# Stazione_Meteo.net
KiCad netlist of a schematic drawn in EAGLE
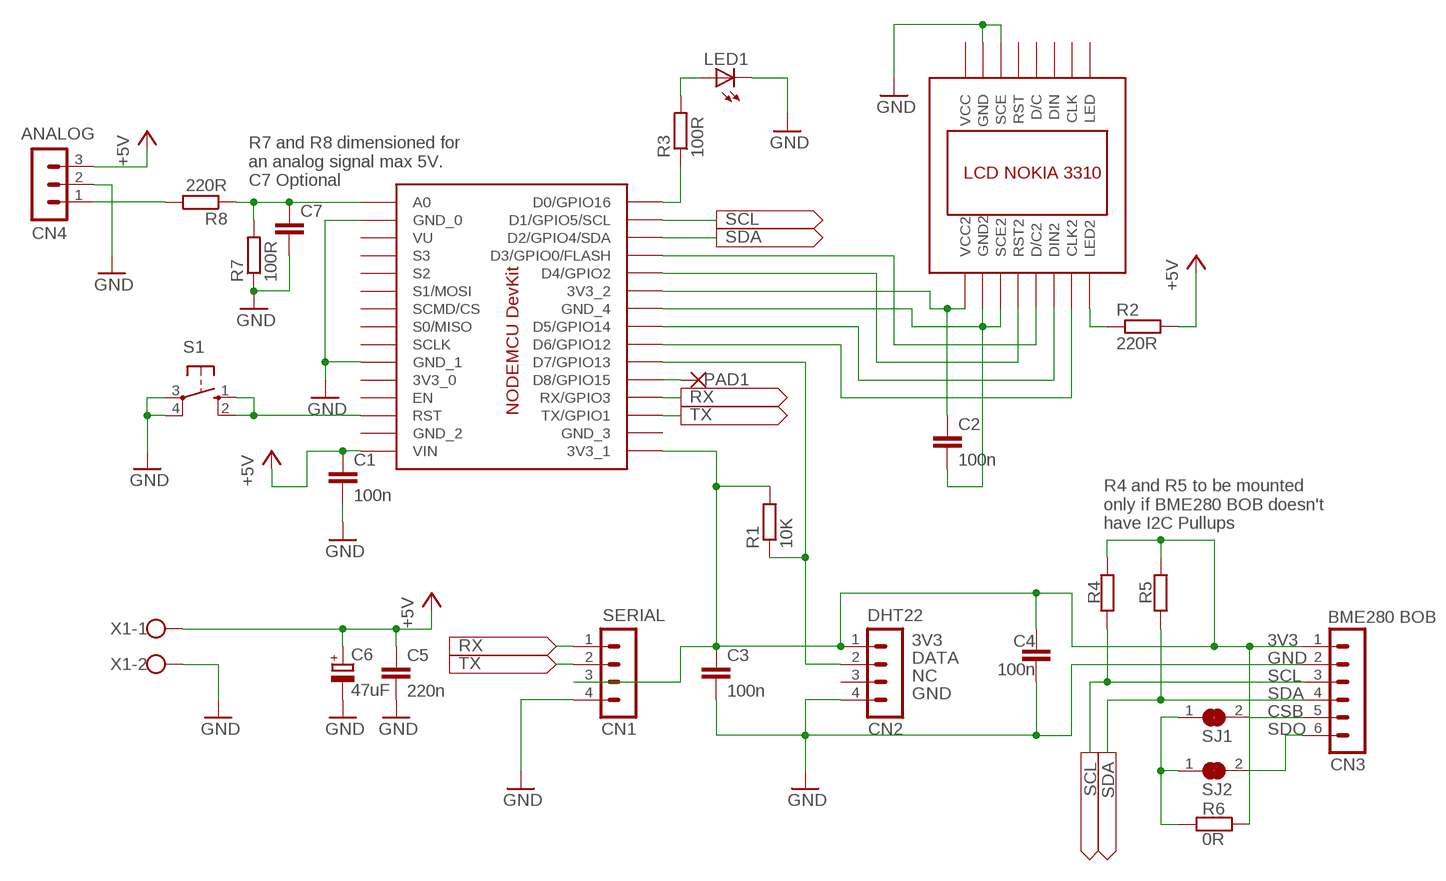
[diagram p0: schematic, sheet 1]

(export (version "E")
  (design (tool "Eeschema 10.0.6"))
  (components
    (comp (ref "C1")
      (value "100n")
      (footprint "eagle-import:C025-024X044")
      (libsource (lib "eagle-import") (part "C-EU025-024X044"))
    )
    (comp (ref "C2")
      (value "100n")
      (footprint "eagle-import:C025-024X044")
      (libsource (lib "eagle-import") (part "C-EU025-024X044"))
    )
    (comp (ref "C3")
      (value "100n")
      (footprint "eagle-import:C025-024X044")
      (libsource (lib "eagle-import") (part "C-EU025-024X044"))
    )
    (comp (ref "C4")
      (value "100n")
      (footprint "eagle-import:C025-024X044")
      (libsource (lib "eagle-import") (part "C-EU025-024X044"))
    )
    (comp (ref "C5")
      (value "220n")
      (footprint "eagle-import:C025-024X044")
      (libsource (lib "eagle-import") (part "C-EU025-024X044"))
    )
    (comp (ref "C6")
      (value "47uF")
      (footprint "eagle-import:E2,5-6E")
      (libsource (lib "eagle-import") (part "CPOL-EUE2,5-6E"))
    )
    (comp (ref "C7")
      (value "C-EU025-024X044")
      (footprint "eagle-import:C025-024X044")
      (libsource (lib "eagle-import") (part "C-EU025-024X044"))
    )
    (comp (ref "CN1")
      (value "MA04-1")
      (footprint "eagle-import:MA04-1")
      (libsource (lib "eagle-import") (part "MA04-1"))
    )
    (comp (ref "CN2")
      (value "MA04-1")
      (footprint "eagle-import:MA04-1")
      (libsource (lib "eagle-import") (part "MA04-1"))
    )
    (comp (ref "CN3")
      (value "MA06-1")
      (footprint "eagle-import:MA06-1")
      (libsource (lib "eagle-import") (part "MA06-1"))
    )
    (comp (ref "CN4")
      (value "MA03-1")
      (footprint "eagle-import:MA03-1")
      (libsource (lib "eagle-import") (part "MA03-1"))
    )
    (comp (ref "LED1")
      (value "LED5MM")
      (footprint "eagle-import:LED5MM")
      (libsource (lib "eagle-import") (part "LED5MM"))
    )
    (comp (ref "PAD1")
      (value "1,6/0,9")
      (footprint "eagle-import:1,6_0,9")
      (libsource (lib "eagle-import") (part "1,6/0,9"))
    )
    (comp (ref "R1")
      (value "10K")
      (footprint "eagle-import:0204_7")
      (libsource (lib "eagle-import") (part "R-EU_0204/7"))
    )
    (comp (ref "R2")
      (value "220R")
      (footprint "eagle-import:0204_7")
      (libsource (lib "eagle-import") (part "R-EU_0204/7"))
    )
    (comp (ref "R3")
      (value "100R")
      (footprint "eagle-import:0204_7")
      (libsource (lib "eagle-import") (part "R-EU_0204/7"))
    )
    (comp (ref "R4")
      (value "R-EU_0204/7")
      (footprint "eagle-import:0204_7")
      (libsource (lib "eagle-import") (part "R-EU_0204/7"))
    )
    (comp (ref "R5")
      (value "R-EU_0204/7")
      (footprint "eagle-import:0204_7")
      (libsource (lib "eagle-import") (part "R-EU_0204/7"))
    )
    (comp (ref "R6")
      (value "0R")
      (footprint "eagle-import:0204_7")
      (libsource (lib "eagle-import") (part "R-EU_0204/7"))
    )
    (comp (ref "R7")
      (value "100R")
      (footprint "eagle-import:0204_7")
      (libsource (lib "eagle-import") (part "R-EU_0204/7"))
    )
    (comp (ref "R8")
      (value "220R")
      (footprint "eagle-import:0204_7")
      (libsource (lib "eagle-import") (part "R-EU_0204/7"))
    )
    (comp (ref "S1")
      (value "10-XX")
      (footprint "eagle-import:B3F-10XX")
      (fields (field (name "MPN") "B3F-1000"))
      (libsource (lib "eagle-import") (part "10-XX"))
    )
    (comp (ref "SJ1") (value "SJ") (footprint "eagle-import:SJ") (libsource (lib "eagle-import") (part "SJ")))
    (comp (ref "SJ2") (value "SJ") (footprint "eagle-import:SJ") (libsource (lib "eagle-import") (part "SJ")))
    (comp (ref "U$1")
      (value "NODEMCU_DEVKIT")
      (footprint "eagle-import:NODEMCU_DEVKIT")
      (libsource (lib "eagle-import") (part "NODEMCU_DEVKIT"))
    )
    (comp (ref "U$2")
      (value "NOKIA_3310/5110_BOB")
      (footprint "eagle-import:NOKIA_3310_5110_BOB")
      (libsource (lib "eagle-import") (part "NOKIA_3310/5110_BOB"))
    )
    (comp (ref "X1")
      (value "W237-102")
      (footprint "eagle-import:W237-102")
      (fields (field (name "MPN") "237-102"))
      (libsource (lib "eagle-import") (part "W237-102"))
    )
  )
  (nets
    (net (code "1") (name "+5V") (class "Default")
      (node (ref "C1") (pin "1") (pinfunction "1_1") (pintype "passive"))
      (node (ref "C5") (pin "1") (pinfunction "1_1") (pintype "passive"))
      (node (ref "C6") (pin "+") (pinfunction "+_+") (pintype "passive"))
      (node (ref "CN4") (pin "3") (pinfunction "3_3") (pintype "passive"))
      (node (ref "R2") (pin "2") (pinfunction "2_2") (pintype "passive"))
      (node (ref "U$1") (pin "VIN") (pinfunction "VIN_VIN") (pintype "power_in"))
      (node (ref "X1") (pin "1") (pinfunction "KL_1") (pintype "passive"))
    )
    (net (code "2") (name "/3V3_0") (class "Default")
      (node (ref "U$1") (pin "3V3_0") (pinfunction "3V3_0_3V3_0") (pintype "power_in"))
    )
    (net (code "3") (name "/GND_2") (class "Default")
      (node (ref "U$1") (pin "GND2") (pinfunction "GND_2_GND2") (pintype "power_in"))
    )
    (net (code "4") (name "/GND_3") (class "Default")
      (node (ref "U$1") (pin "GND3") (pinfunction "GND_3_GND3") (pintype "power_in"))
    )
    (net (code "5") (name "/LED") (class "Default")
      (node (ref "U$2") (pin "LED") (pinfunction "LED_LED") (pintype "power_in"))
    )
    (net (code "6") (name "/RX") (class "Default")
      (node (ref "CN1") (pin "1") (pinfunction "1_1") (pintype "passive"))
      (node (ref "U$1") (pin "RX/GPIO3") (pinfunction "RX/GPIO3_RX/GPIO3") (pintype "bidirectional"))
    )
    (net (code "7") (name "/SCL") (class "Default")
      (node (ref "CN3") (pin "3") (pinfunction "3_3") (pintype "passive"))
      (node (ref "R4") (pin "1") (pinfunction "1_1") (pintype "passive"))
      (node (ref "U$1") (pin "D1/GPIO5") (pinfunction "D1/GPIO5/SCL_D1/GPIO5") (pintype "bidirectional"))
    )
    (net (code "8") (name "/SDA") (class "Default")
      (node (ref "CN3") (pin "4") (pinfunction "4_4") (pintype "passive"))
      (node (ref "R5") (pin "1") (pinfunction "1_1") (pintype "passive"))
      (node (ref "U$1") (pin "D2/GPIO4") (pinfunction "D2/GPIO4/SDA_D2/GPIO4") (pintype "bidirectional"))
    )
    (net (code "9") (name "/TX") (class "Default")
      (node (ref "CN1") (pin "2") (pinfunction "2_2") (pintype "passive"))
      (node (ref "U$1") (pin "TX/GPIO1") (pinfunction "TX/GPIO1_TX/GPIO1") (pintype "bidirectional"))
    )
    (net (code "10") (name "/VCC") (class "Default")
      (node (ref "U$2") (pin "VCC") (pinfunction "VCC_VCC") (pintype "power_in"))
    )
    (net (code "11") (name "GND") (class "Default")
      (node (ref "C1") (pin "2") (pinfunction "2_2") (pintype "passive"))
      (node (ref "C3") (pin "2") (pinfunction "2_2") (pintype "passive"))
      (node (ref "C4") (pin "2") (pinfunction "2_2") (pintype "passive"))
      (node (ref "C5") (pin "2") (pinfunction "2_2") (pintype "passive"))
      (node (ref "C6") (pin "-") (pinfunction "-_-") (pintype "passive"))
      (node (ref "C7") (pin "2") (pinfunction "2_2") (pintype "passive"))
      (node (ref "CN1") (pin "4") (pinfunction "4_4") (pintype "passive"))
      (node (ref "CN2") (pin "4") (pinfunction "4_4") (pintype "passive"))
      (node (ref "CN3") (pin "2") (pinfunction "2_2") (pintype "passive"))
      (node (ref "CN4") (pin "2") (pinfunction "2_2") (pintype "passive"))
      (node (ref "LED1") (pin "K") (pinfunction "C_K") (pintype "passive"))
      (node (ref "R7") (pin "1") (pinfunction "1_1") (pintype "passive"))
      (node (ref "S1") (pin "3") (pinfunction "P_3") (pintype "passive"))
      (node (ref "S1") (pin "4") (pinfunction "P1_4") (pintype "passive"))
      (node (ref "U$1") (pin "GND0") (pinfunction "GND_0_GND0") (pintype "power_in"))
      (node (ref "U$1") (pin "GND1") (pinfunction "GND_1_GND1") (pintype "power_in"))
      (node (ref "U$2") (pin "GND") (pinfunction "GND_GND") (pintype "power_in"))
      (node (ref "U$2") (pin "SCE") (pinfunction "SCE_SCE") (pintype "input"))
      (node (ref "X1") (pin "2") (pinfunction "KL_2") (pintype "passive"))
    )
    (net (code "12") (name "Net-(C2-Pad1)") (class "Default")
      (node (ref "C2") (pin "1") (pinfunction "1_1") (pintype "passive"))
      (node (ref "U$1") (pin "3V3_2") (pinfunction "3V3_2_3V3_2") (pintype "power_in"))
      (node (ref "U$2") (pin "VCC2") (pinfunction "VCC2_VCC2") (pintype "power_in"))
    )
    (net (code "13") (name "Net-(C3-Pad1)") (class "Default")
      (node (ref "C3") (pin "1") (pinfunction "1_1") (pintype "passive"))
      (node (ref "C4") (pin "1") (pinfunction "1_1") (pintype "passive"))
      (node (ref "CN1") (pin "3") (pinfunction "3_3") (pintype "passive"))
      (node (ref "CN2") (pin "1") (pinfunction "1_1") (pintype "passive"))
      (node (ref "CN3") (pin "1") (pinfunction "1_1") (pintype "passive"))
      (node (ref "R1") (pin "2") (pinfunction "2_2") (pintype "passive"))
      (node (ref "R4") (pin "2") (pinfunction "2_2") (pintype "passive"))
      (node (ref "R5") (pin "2") (pinfunction "2_2") (pintype "passive"))
      (node (ref "R6") (pin "1") (pinfunction "1_1") (pintype "passive"))
      (node (ref "U$1") (pin "3V3_1") (pinfunction "3V3_1_3V3_1") (pintype "power_in"))
    )
    (net (code "14") (name "Net-(C7-Pad1)") (class "Default")
      (node (ref "C7") (pin "1") (pinfunction "1_1") (pintype "passive"))
      (node (ref "R7") (pin "2") (pinfunction "2_2") (pintype "passive"))
      (node (ref "R8") (pin "1") (pinfunction "1_1") (pintype "passive"))
      (node (ref "U$1") (pin "A0") (pinfunction "A0_A0") (pintype "bidirectional"))
    )
    (net (code "15") (name "Net-(CN2-Pad2)") (class "Default")
      (node (ref "CN2") (pin "2") (pinfunction "2_2") (pintype "passive"))
      (node (ref "R1") (pin "1") (pinfunction "1_1") (pintype "passive"))
      (node (ref "U$1") (pin "D7/GPIO13") (pinfunction "D7/GPIO13_D7/GPIO13") (pintype "bidirectional"))
    )
    (net (code "16") (name "Net-(CN3-Pad5)") (class "Default")
      (node (ref "CN3") (pin "5") (pinfunction "5_5") (pintype "passive"))
      (node (ref "SJ1") (pin "2") (pinfunction "2_2") (pintype "passive"))
    )
    (net (code "17") (name "Net-(CN3-Pad6)") (class "Default")
      (node (ref "CN3") (pin "6") (pinfunction "6_6") (pintype "passive"))
      (node (ref "SJ2") (pin "2") (pinfunction "2_2") (pintype "passive"))
    )
    (net (code "18") (name "Net-(CN4-Pad1)") (class "Default")
      (node (ref "CN4") (pin "1") (pinfunction "1_1") (pintype "passive"))
      (node (ref "R8") (pin "2") (pinfunction "2_2") (pintype "passive"))
    )
    (net (code "19") (name "Net-(LED1-PadA)") (class "Default")
      (node (ref "LED1") (pin "A") (pinfunction "A_A") (pintype "passive"))
      (node (ref "R3") (pin "2") (pinfunction "2_2") (pintype "passive"))
    )
    (net (code "20") (name "Net-(PAD1-P)") (class "Default")
      (node (ref "PAD1") (pin "1") (pinfunction "P_1") (pintype "passive"))
      (node (ref "U$1") (pin "D8/GPIO15") (pinfunction "D8/GPIO15_D8/GPIO15") (pintype "bidirectional"))
    )
    (net (code "21") (name "Net-(R2-Pad1)") (class "Default")
      (node (ref "R2") (pin "1") (pinfunction "1_1") (pintype "passive"))
      (node (ref "U$2") (pin "LED2") (pinfunction "LED2_LED2") (pintype "power_in"))
    )
    (net (code "22") (name "Net-(R3-Pad1)") (class "Default")
      (node (ref "R3") (pin "1") (pinfunction "1_1") (pintype "passive"))
      (node (ref "U$1") (pin "D0/GPIO16") (pinfunction "D0/GPIO16_D0/GPIO16") (pintype "bidirectional"))
    )
    (net (code "23") (name "Net-(R6-Pad2)") (class "Default")
      (node (ref "R6") (pin "2") (pinfunction "2_2") (pintype "passive"))
      (node (ref "SJ1") (pin "1") (pinfunction "1_1") (pintype "passive"))
      (node (ref "SJ2") (pin "1") (pinfunction "1_1") (pintype "passive"))
    )
    (net (code "24") (name "Net-(S1-S)") (class "Default")
      (node (ref "S1") (pin "1") (pinfunction "S_1") (pintype "passive"))
      (node (ref "S1") (pin "2") (pinfunction "S1_2") (pintype "passive"))
      (node (ref "U$1") (pin "RST") (pinfunction "RST_RST") (pintype "bidirectional"))
    )
    (net (code "25") (name "Net-(U$1-D3{slash}GPIO0{slash}FLASH)") (class "Default")
      (node (ref "U$1") (pin "D3/GPIO0") (pinfunction "D3/GPIO0/FLASH_D3/GPIO0") (pintype "bidirectional"))
      (node (ref "U$2") (pin "D/C2") (pinfunction "D/C2_D/C2") (pintype "input"))
    )
    (net (code "26") (name "Net-(U$1-GND_4)") (class "Default")
      (node (ref "C2") (pin "2") (pinfunction "2_2") (pintype "passive"))
      (node (ref "U$1") (pin "GND4") (pinfunction "GND_4_GND4") (pintype "power_in"))
      (node (ref "U$2") (pin "GND2") (pinfunction "GND2_GND2") (pintype "power_in"))
      (node (ref "U$2") (pin "SCE2") (pinfunction "SCE2_SCE2") (pintype "input"))
    )
    (net (code "27") (name "Net-(U$1-PadD4{slash}GPIO2)") (class "Default")
      (node (ref "U$1") (pin "D4/GPIO2") (pinfunction "D4/GPIO2_D4/GPIO2") (pintype "bidirectional"))
      (node (ref "U$2") (pin "RST2") (pinfunction "RST2_RST2") (pintype "input"))
    )
    (net (code "28") (name "Net-(U$1-PadD5{slash}GPIO14)") (class "Default")
      (node (ref "U$1") (pin "D5/GPIO14") (pinfunction "D5/GPIO14_D5/GPIO14") (pintype "bidirectional"))
      (node (ref "U$2") (pin "DIN2") (pinfunction "DIN2_DIN2") (pintype "input"))
    )
    (net (code "29") (name "Net-(U$1-PadD6{slash}GPIO12)") (class "Default")
      (node (ref "U$1") (pin "D6/GPIO12") (pinfunction "D6/GPIO12_D6/GPIO12") (pintype "bidirectional"))
      (node (ref "U$2") (pin "CLK2") (pinfunction "CLK2_CLK2") (pintype "input"))
    )
    (net (code "30") (name "unconnected-(CN2-Pad3)") (class "Default")
      (node (ref "CN2") (pin "3") (pinfunction "3_3") (pintype "passive"))
    )
    (net (code "31") (name "unconnected-(U$1-PadEN)") (class "Default")
      (node (ref "U$1") (pin "EN") (pinfunction "EN_EN") (pintype "bidirectional"))
    )
    (net (code "32") (name "unconnected-(U$1-PadS2)") (class "Default")
      (node (ref "U$1") (pin "S2") (pinfunction "S2_S2") (pintype "bidirectional"))
    )
    (net (code "33") (name "unconnected-(U$1-PadS3)") (class "Default")
      (node (ref "U$1") (pin "S3") (pinfunction "S3_S3") (pintype "bidirectional"))
    )
    (net (code "34") (name "unconnected-(U$1-PadVU)") (class "Default")
      (node (ref "U$1") (pin "VU") (pinfunction "VU_VU") (pintype "bidirectional"))
    )
    (net (code "35") (name "unconnected-(U$1-S0{slash}MISO-PadS0)") (class "Default")
      (node (ref "U$1") (pin "S0") (pinfunction "S0/MISO_S0") (pintype "bidirectional"))
    )
    (net (code "36") (name "unconnected-(U$1-S1{slash}MOSI-PadS1)") (class "Default")
      (node (ref "U$1") (pin "S1") (pinfunction "S1/MOSI_S1") (pintype "bidirectional"))
    )
    (net (code "37") (name "unconnected-(U$1-SCLK-PadSC)") (class "Default")
      (node (ref "U$1") (pin "SC") (pinfunction "SCLK_SC") (pintype "bidirectional"))
    )
    (net (code "38") (name "unconnected-(U$1-SCMD{slash}CS-PadSK)") (class "Default")
      (node (ref "U$1") (pin "SK") (pinfunction "SCMD/CS_SK") (pintype "bidirectional"))
    )
    (net (code "39") (name "unconnected-(U$2-PadCLK)") (class "Default")
      (node (ref "U$2") (pin "CLK") (pinfunction "CLK_CLK") (pintype "input"))
    )
    (net (code "40") (name "unconnected-(U$2-PadDIN)") (class "Default")
      (node (ref "U$2") (pin "DIN") (pinfunction "DIN_DIN") (pintype "input"))
    )
    (net (code "41") (name "unconnected-(U$2-PadD{slash}C)") (class "Default")
      (node (ref "U$2") (pin "D/C") (pinfunction "D/C_D/C") (pintype "input"))
    )
    (net (code "42") (name "unconnected-(U$2-PadRST)") (class "Default")
      (node (ref "U$2") (pin "RST") (pinfunction "RST_RST") (pintype "input"))
    )
  )
)
